# EDA.net
KiCad netlist of a schematic drawn in EasyEDA Pro
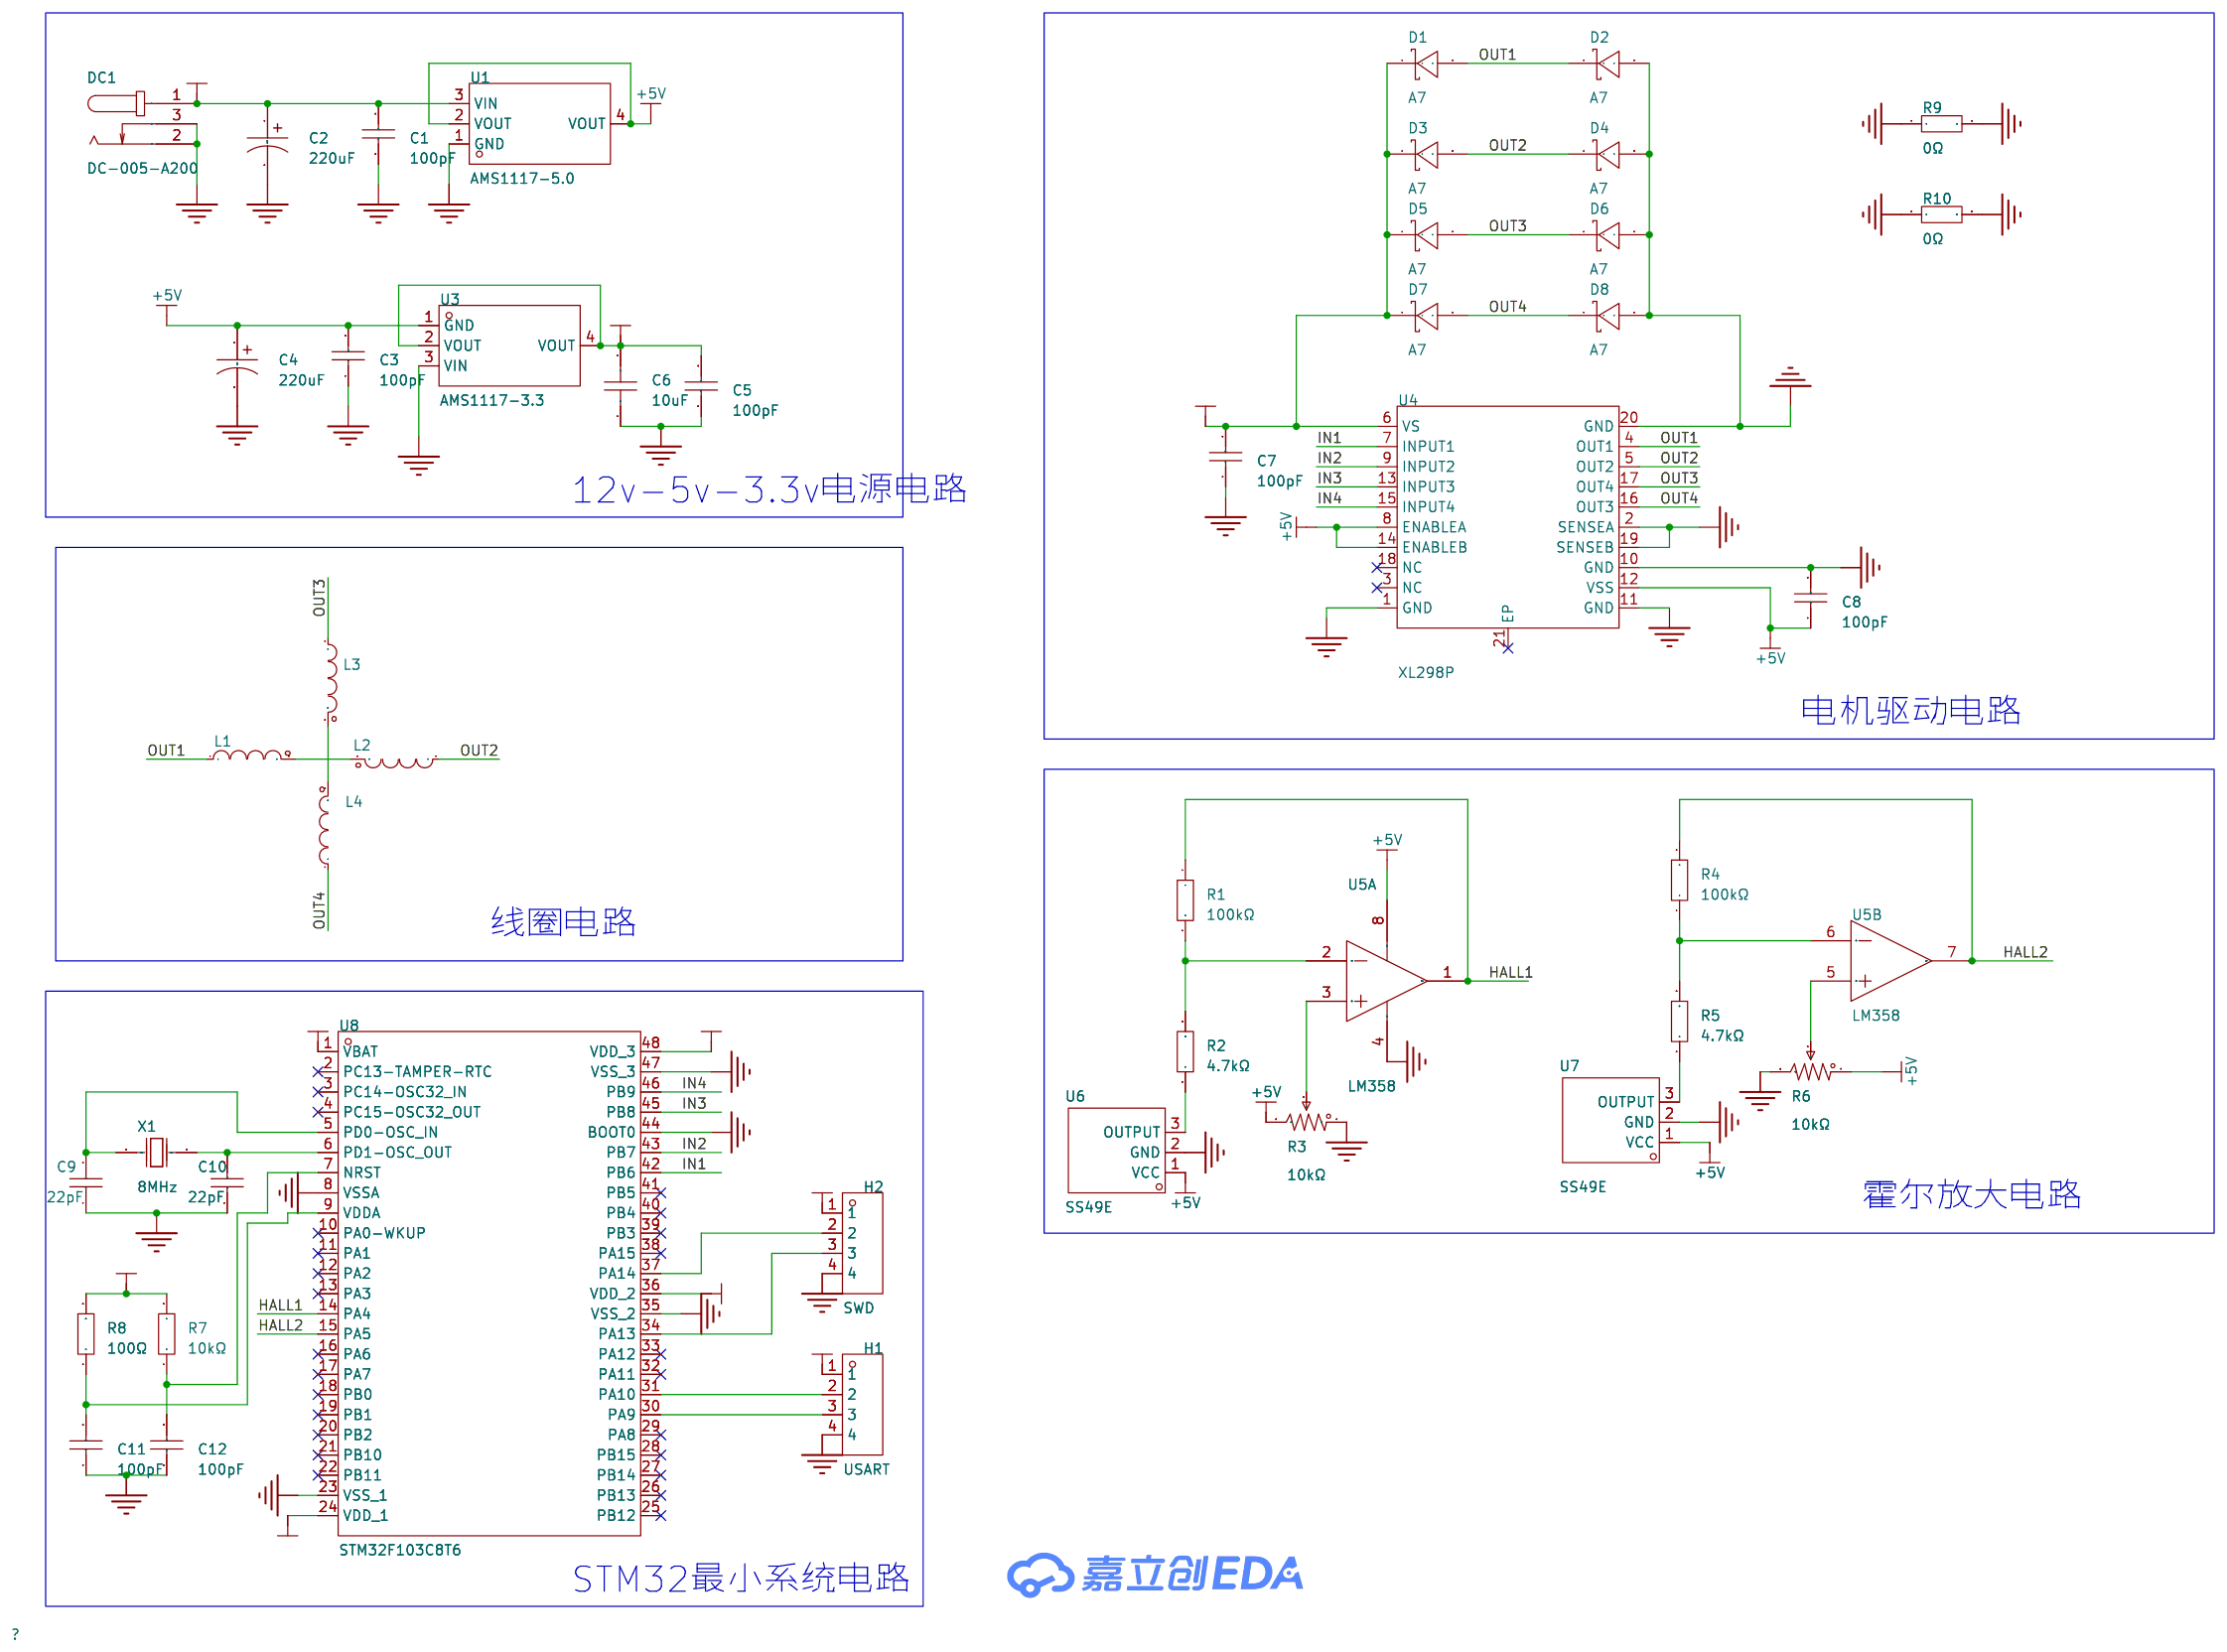
[diagram p0: schematic sheet]

(export (version "E")
  (design (tool "Eeschema 10.0.6"))
  (components
    (comp (ref "C1")
      (value "100pF")
      (footprint "easyedapro:C0805")
      (description "容值:100pF;精度:±5%;额定电压:50V;材质(温度系数):C0G;")
      (fields
        (field (name "Manufacturer Part") "CL21C101JBANNNC")
        (field (name "Manufacturer") "SAMSUNG(三星)")
      )
      (libsource (lib "easyedapro") (part "CL21C101JBANNNC"))
    )
    (comp (ref "C2")
      (value "220uF")
      (footprint "easyedapro:CAP-SMD_BD10.0-L10.3-W10.3-LS11.3-FD")
      (description "容值:220uF;精度:±20%;额定电压:50V;")
      (fields (field (name "Manufacturer Part") "HV1H227M1010PZ") (field (name "Manufacturer") "HONOR(荣誉)"))
      (libsource (lib "easyedapro") (part "HV1H227M1010PZ"))
    )
    (comp (ref "C3")
      (value "100pF")
      (footprint "easyedapro:C0805")
      (description "容值:100pF;精度:±5%;额定电压:50V;材质(温度系数):C0G;")
      (fields
        (field (name "Manufacturer Part") "CL21C101JBANNNC")
        (field (name "Manufacturer") "SAMSUNG(三星)")
      )
      (libsource (lib "easyedapro") (part "CL21C101JBANNNC"))
    )
    (comp (ref "C4")
      (value "220uF")
      (footprint "easyedapro:CAP-SMD_BD10.0-L10.3-W10.3-LS11.3-FD")
      (description "容值:220uF;精度:±20%;额定电压:50V;")
      (fields (field (name "Manufacturer Part") "HV1H227M1010PZ") (field (name "Manufacturer") "HONOR(荣誉)"))
      (libsource (lib "easyedapro") (part "HV1H227M1010PZ"))
    )
    (comp (ref "C5")
      (value "100pF")
      (footprint "easyedapro:C0805")
      (description "容值:100pF;精度:±5%;额定电压:50V;材质(温度系数):C0G;")
      (fields
        (field (name "Manufacturer Part") "CL21C101JBANNNC")
        (field (name "Manufacturer") "SAMSUNG(三星)")
      )
      (libsource (lib "easyedapro") (part "CL21C101JBANNNC"))
    )
    (comp (ref "C6")
      (value "10uF")
      (footprint "easyedapro:C0805")
      (description "容值:10uF;精度:±10%;额定电压:50V;材质(温度系数):X5R;")
      (fields
        (field (name "Manufacturer Part") "GRM21BR61H106KE43L")
        (field (name "Manufacturer") "muRata(村田)")
      )
      (libsource (lib "easyedapro") (part "GRM21BR61H106KE43L"))
    )
    (comp (ref "C7")
      (value "100pF")
      (footprint "easyedapro:C0805")
      (description "容值:100pF;精度:±5%;额定电压:50V;材质(温度系数):C0G;")
      (fields
        (field (name "Manufacturer Part") "CL21C101JBANNNC")
        (field (name "Manufacturer") "SAMSUNG(三星)")
      )
      (libsource (lib "easyedapro") (part "CL21C101JBANNNC"))
    )
    (comp (ref "C8")
      (value "100pF")
      (footprint "easyedapro:C0805")
      (description "容值:100pF;精度:±5%;额定电压:50V;材质(温度系数):C0G;")
      (fields
        (field (name "Manufacturer Part") "CL21C101JBANNNC")
        (field (name "Manufacturer") "SAMSUNG(三星)")
      )
      (libsource (lib "easyedapro") (part "CL21C101JBANNNC"))
    )
    (comp (ref "C9")
      (value "22pF")
      (footprint "easyedapro:C0805")
      (description "容值:22pF;精度:±5%;额定电压:50V;材质(温度系数):C0G;")
      (fields
        (field (name "Manufacturer Part") "CL21C220JBANNNC")
        (field (name "Manufacturer") "SAMSUNG(三星)")
      )
      (libsource (lib "easyedapro") (part "CL21C220JBANNNC"))
    )
    (comp (ref "C10")
      (value "22pF")
      (footprint "easyedapro:C0805")
      (description "容值:22pF;精度:±5%;额定电压:50V;材质(温度系数):C0G;")
      (fields
        (field (name "Manufacturer Part") "CL21C220JBANNNC")
        (field (name "Manufacturer") "SAMSUNG(三星)")
      )
      (libsource (lib "easyedapro") (part "CL21C220JBANNNC"))
    )
    (comp (ref "C11")
      (value "100pF")
      (footprint "easyedapro:C0805")
      (description "容值:100pF;精度:±5%;额定电压:50V;材质(温度系数):C0G;")
      (fields
        (field (name "Manufacturer Part") "CL21C101JBANNNC")
        (field (name "Manufacturer") "SAMSUNG(三星)")
      )
      (libsource (lib "easyedapro") (part "CL21C101JBANNNC"))
    )
    (comp (ref "C12")
      (value "100pF")
      (footprint "easyedapro:C0805")
      (description "容值:100pF;精度:±5%;额定电压:50V;材质(温度系数):C0G;")
      (fields
        (field (name "Manufacturer Part") "CL21C101JBANNNC")
        (field (name "Manufacturer") "SAMSUNG(三星)")
      )
      (libsource (lib "easyedapro") (part "CL21C101JBANNNC"))
    )
    (comp (ref "D1")
      (value "A7")
      (footprint "easyedapro:SOD-123FL_L2.8-W1.8-LS3.7-RD")
      (description "二极管配置:独立式;正向压降(Vf):1.1V@1A;直流反向耐压(Vr):1kV;整流电流:1A;")
      (fields (field (name "Manufacturer") "GOODWORK(固得沃克)"))
      (libsource (lib "easyedapro") (part "A7_C2891324"))
    )
    (comp (ref "D2")
      (value "A7")
      (footprint "easyedapro:SOD-123FL_L2.8-W1.8-LS3.7-RD")
      (description "二极管配置:独立式;正向压降(Vf):1.1V@1A;直流反向耐压(Vr):1kV;整流电流:1A;")
      (fields (field (name "Manufacturer") "GOODWORK(固得沃克)"))
      (libsource (lib "easyedapro") (part "A7_C2891324"))
    )
    (comp (ref "D3")
      (value "A7")
      (footprint "easyedapro:SOD-123FL_L2.8-W1.8-LS3.7-RD")
      (description "二极管配置:独立式;正向压降(Vf):1.1V@1A;直流反向耐压(Vr):1kV;整流电流:1A;")
      (fields (field (name "Manufacturer") "GOODWORK(固得沃克)"))
      (libsource (lib "easyedapro") (part "A7_C2891324"))
    )
    (comp (ref "D4")
      (value "A7")
      (footprint "easyedapro:SOD-123FL_L2.8-W1.8-LS3.7-RD")
      (description "二极管配置:独立式;正向压降(Vf):1.1V@1A;直流反向耐压(Vr):1kV;整流电流:1A;")
      (fields (field (name "Manufacturer") "GOODWORK(固得沃克)"))
      (libsource (lib "easyedapro") (part "A7_C2891324"))
    )
    (comp (ref "D5")
      (value "A7")
      (footprint "easyedapro:SOD-123FL_L2.8-W1.8-LS3.7-RD")
      (description "二极管配置:独立式;正向压降(Vf):1.1V@1A;直流反向耐压(Vr):1kV;整流电流:1A;")
      (fields (field (name "Manufacturer") "GOODWORK(固得沃克)"))
      (libsource (lib "easyedapro") (part "A7_C2891324"))
    )
    (comp (ref "D6")
      (value "A7")
      (footprint "easyedapro:SOD-123FL_L2.8-W1.8-LS3.7-RD")
      (description "二极管配置:独立式;正向压降(Vf):1.1V@1A;直流反向耐压(Vr):1kV;整流电流:1A;")
      (fields (field (name "Manufacturer") "GOODWORK(固得沃克)"))
      (libsource (lib "easyedapro") (part "A7_C2891324"))
    )
    (comp (ref "D7")
      (value "A7")
      (footprint "easyedapro:SOD-123FL_L2.8-W1.8-LS3.7-RD")
      (description "二极管配置:独立式;正向压降(Vf):1.1V@1A;直流反向耐压(Vr):1kV;整流电流:1A;")
      (fields (field (name "Manufacturer") "GOODWORK(固得沃克)"))
      (libsource (lib "easyedapro") (part "A7_C2891324"))
    )
    (comp (ref "D8")
      (value "A7")
      (footprint "easyedapro:SOD-123FL_L2.8-W1.8-LS3.7-RD")
      (description "二极管配置:独立式;正向压降(Vf):1.1V@1A;直流反向耐压(Vr):1kV;整流电流:1A;")
      (fields (field (name "Manufacturer") "GOODWORK(固得沃克)"))
      (libsource (lib "easyedapro") (part "A7_C2891324"))
    )
    (comp (ref "DC1")
      (value "DC-005-A200")
      (footprint "easyedapro:DC-IN-TH_DC-005-A200")
      (description "连接器类型:DC电源插座;安装方式:弯插;触点内径:2mm;触点外径:6.4mm;额定电流:3A;额定电压:30V;工作温度范围:-20°C~+70°C;")
      (fields (field (name "Manufacturer") "XUNPU(讯普)"))
      (libsource (lib "easyedapro") (part "DC-005-A200"))
    )
    (comp (ref "H1")
      (value "USART")
      (footprint "easyedapro:HDR-TH_4P-P2.54-V-M")
      (fields (field (name "Manufacturer") "XFCN(兴飞)"))
      (libsource (lib "easyedapro") (part "PZ254V-11-04P_C2691448"))
    )
    (comp (ref "H2")
      (value "SWD")
      (footprint "easyedapro:HDR-TH_4P-P2.54-V-M")
      (fields (field (name "Manufacturer") "XFCN(兴飞)"))
      (libsource (lib "easyedapro") (part "PZ254V-11-04P_C2691448"))
    )
    (comp (ref "L1")
      (value "~")
      (footprint "easyedapro:L_INVERTER2_2.1")
      (libsource (lib "easyedapro") (part "L-6Ω-3.54"))
    )
    (comp (ref "L2")
      (value "~")
      (footprint "easyedapro:L_INVERTER2_2.1")
      (libsource (lib "easyedapro") (part "L-6Ω-3.54"))
    )
    (comp (ref "L3")
      (value "~")
      (footprint "easyedapro:L_INVERTER2_2.1")
      (libsource (lib "easyedapro") (part "L-6Ω-3.54"))
    )
    (comp (ref "L4")
      (value "~")
      (footprint "easyedapro:L_INVERTER2_2.1")
      (libsource (lib "easyedapro") (part "L-6Ω-3.54"))
    )
    (comp (ref "R1")
      (value "100kΩ")
      (footprint "easyedapro:R0805")
      (description "电阻类型:厚膜电阻;阻值:100kΩ;精度:±1%;功率:125mW;最大工作电压:150V;温度系数:±100ppm/°C;")
      (fields
        (field (name "Manufacturer Part") "0805W8F1003T5E")
        (field (name "Manufacturer") "UNI-ROYAL(厚声)")
      )
      (libsource (lib "easyedapro") (part "0805W8F1003T5E_C149504"))
    )
    (comp (ref "R2")
      (value "4.7kΩ")
      (footprint "easyedapro:R0805")
      (description "电阻类型:厚膜电阻;阻值:4.7kΩ;精度:±1%;功率:125mW;最大工作电压:150V;温度系数:±100ppm/°C;")
      (fields
        (field (name "Manufacturer Part") "0805W8F4701T5E")
        (field (name "Manufacturer") "UNI-ROYAL(厚声)")
      )
      (libsource (lib "easyedapro") (part "0805W8F4701T5E"))
    )
    (comp (ref "R3")
      (value "10kΩ")
      (footprint "easyedapro:RES-ADJ-TH_3P-L10.0-W10.0-P2.50-L")
      (description "阻值:10kΩ;精度:±10%;")
      (fields (field (name "Manufacturer Part") "3296W-1-103") (field (name "Manufacturer") "BOCHEN(博晨)"))
      (libsource (lib "easyedapro") (part "3296W-1-103"))
    )
    (comp (ref "R4")
      (value "100kΩ")
      (footprint "easyedapro:R0805")
      (description "电阻类型:厚膜电阻;阻值:100kΩ;精度:±1%;功率:125mW;最大工作电压:150V;温度系数:±100ppm/°C;")
      (fields
        (field (name "Manufacturer Part") "0805W8F1003T5E")
        (field (name "Manufacturer") "UNI-ROYAL(厚声)")
      )
      (libsource (lib "easyedapro") (part "0805W8F1003T5E_C149504"))
    )
    (comp (ref "R5")
      (value "4.7kΩ")
      (footprint "easyedapro:R0805")
      (description "电阻类型:厚膜电阻;阻值:4.7kΩ;精度:±1%;功率:125mW;最大工作电压:150V;温度系数:±100ppm/°C;")
      (fields
        (field (name "Manufacturer Part") "0805W8F4701T5E")
        (field (name "Manufacturer") "UNI-ROYAL(厚声)")
      )
      (libsource (lib "easyedapro") (part "0805W8F4701T5E"))
    )
    (comp (ref "R6")
      (value "10kΩ")
      (footprint "easyedapro:RES-ADJ-TH_3P-L10.0-W10.0-P2.50-L")
      (description "阻值:10kΩ;精度:±10%;")
      (fields (field (name "Manufacturer Part") "3296W-1-103") (field (name "Manufacturer") "BOCHEN(博晨)"))
      (libsource (lib "easyedapro") (part "3296W-1-103"))
    )
    (comp (ref "R7")
      (value "10kΩ")
      (footprint "easyedapro:R0805")
      (description "电阻类型:厚膜电阻;阻值:10kΩ;精度:±1%;功率:125mW;最大工作电压:150V;温度系数:±100ppm/°C;")
      (fields
        (field (name "Manufacturer Part") "0805W8F1002T5E")
        (field (name "Manufacturer") "UNI-ROYAL(厚声)")
      )
      (libsource (lib "easyedapro") (part "0805W8F1002T5E"))
    )
    (comp (ref "R8")
      (value "100Ω")
      (footprint "easyedapro:R0805")
      (description "电阻类型:厚膜电阻;阻值:100Ω;精度:±1%;功率:125mW;最大工作电压:150V;温度系数:±100ppm/°C;")
      (fields
        (field (name "Manufacturer Part") "0805W8F1000T5E")
        (field (name "Manufacturer") "UNI-ROYAL(厚声)")
      )
      (libsource (lib "easyedapro") (part "0805W8F1000T5E"))
    )
    (comp (ref "R9")
      (value "0Ω")
      (footprint "easyedapro:R0805")
      (description "电阻类型:厚膜电阻;阻值:0Ω;精度:±1%;功率:125mW;最大工作电压:150V;温度系数:±800ppm/°C;")
      (fields
        (field (name "Manufacturer Part") "0805W8F0000T5E")
        (field (name "Manufacturer") "UNI-ROYAL(厚声)")
      )
      (libsource (lib "easyedapro") (part "0805W8F0000T5E"))
    )
    (comp (ref "R10")
      (value "0Ω")
      (footprint "easyedapro:R0805")
      (description "电阻类型:厚膜电阻;阻值:0Ω;精度:±1%;功率:125mW;最大工作电压:150V;温度系数:±800ppm/°C;")
      (fields
        (field (name "Manufacturer Part") "0805W8F0000T5E")
        (field (name "Manufacturer") "UNI-ROYAL(厚声)")
      )
      (libsource (lib "easyedapro") (part "0805W8F0000T5E"))
    )
    (comp (ref "U1")
      (value "AMS1117-5.0")
      (footprint "easyedapro:SOT-223_L6.5-W3.5-P2.30-LS7.0-BR")
      (description "输出类型:固定;最大输入电压:12V;输出电压:5V;最大输出电流:1A;电源纹波抑制比(PSRR):68dB@(120Hz);输出极性:正极;")
      (fields (field (name "Manufacturer") "AMS"))
      (libsource (lib "easyedapro") (part "AMS1117-5.0"))
    )
    (comp (ref "U3")
      (value "AMS1117-3.3")
      (footprint "easyedapro:SOT-223-3_L6.5-W3.4-P2.30-LS7.0-BR")
      (description "输出类型:固定;最大输入电压:-;输出电压:3.3V;最大输出电流:1A;电源纹波抑制比(PSRR):72dB@(120Hz);输出极性:正极;")
      (fields (field (name "Manufacturer") "AMS"))
      (libsource (lib "easyedapro") (part "AMS1117-3.3"))
    )
    (comp (ref "U4")
      (value "XL298P")
      (footprint "easyedapro:HSOP-20_L15.9-W11.0-P1.27-LS14.2-BL-EP")
      (fields (field (name "Manufacturer") "XINLUDA(信路达)"))
      (libsource (lib "easyedapro") (part "XL298P"))
    )
    (comp (ref "U5")
      (value "LM358")
      (footprint "easyedapro:SOP-8_L4.9-W3.9-P1.27-LS6.0-BL")
      (description "放大器数:双路;增益带宽积(GBP):1.2MHz;输入偏置电流(Ib):50nA;输入失调电压(Vos):5mV;")
      (fields (field (name "Manufacturer") "MSKSEMI(美森科)"))
      (libsource (lib "easyedapro") (part "LM358_C5252902"))
    )
    (comp (ref "U6")
      (value "SS49E")
      (footprint "easyedapro:TO-92S_3P-L4.1-W1.6-P1.27-L")
      (description "线性霍尔效应传感器")
      (fields (field (name "Manufacturer") "Honeywell(霍尼韦尔)"))
      (libsource (lib "easyedapro") (part "SS49E"))
    )
    (comp (ref "U7")
      (value "SS49E")
      (footprint "easyedapro:TO-92S_3P-L4.1-W1.6-P1.27-L")
      (description "线性霍尔效应传感器")
      (fields (field (name "Manufacturer") "Honeywell(霍尼韦尔)"))
      (libsource (lib "easyedapro") (part "SS49E"))
    )
    (comp (ref "U8")
      (value "STM32F103C8T6")
      (footprint "easyedapro:LQFP-48_L7.0-W7.0-P0.50-LS9.0-BL")
      (description "CPU内核:ARM-M3;CPU最大主频:72MHz;应用领域:-;")
      (fields (field (name "Manufacturer") "ST(意法半导体)"))
      (libsource (lib "easyedapro") (part "STM32F103C8T6"))
    )
    (comp (ref "X1")
      (value "8MHz")
      (footprint "easyedapro:CRYSTAL-SMD_L11.5-W4.8-LS12.7")
      (description "晶振类型:贴片晶振;频率:8MHz;常温频差:±20ppm;外接负载电容:20pF;频率稳定度(全温):±30ppm;")
      (fields (field (name "Manufacturer Part") "X49SM8MSD2SC") (field (name "Manufacturer") "YXC(扬兴晶振)"))
      (libsource (lib "easyedapro") (part "X49SM8MSD2SC"))
    )
  )
  (nets
    (net (code "1") (name "+3.3V") (class "Default")
      (node (ref "C5") (pin "2") (pinfunction "2_2") (pintype "input"))
      (node (ref "C6") (pin "2") (pinfunction "2_2") (pintype "unspecified"))
      (node (ref "H1") (pin "1") (pinfunction "1_1") (pintype "unspecified"))
      (node (ref "H2") (pin "1") (pinfunction "1_1") (pintype "unspecified"))
      (node (ref "R7") (pin "2") (pinfunction "2_2") (pintype "input"))
      (node (ref "R8") (pin "2") (pinfunction "2_2") (pintype "input"))
      (node (ref "U3") (pin "2") (pinfunction "VOUT_2") (pintype "unspecified"))
      (node (ref "U3") (pin "4") (pinfunction "VOUT_4") (pintype "unspecified"))
      (node (ref "U8") (pin "1") (pinfunction "VBAT_1") (pintype "unspecified"))
      (node (ref "U8") (pin "24") (pinfunction "VDD_1_24") (pintype "unspecified"))
      (node (ref "U8") (pin "36") (pinfunction "VDD_2_36") (pintype "unspecified"))
      (node (ref "U8") (pin "48") (pinfunction "VDD_3_48") (pintype "unspecified"))
    )
    (net (code "2") (name "+5V") (class "Default")
      (node (ref "C3") (pin "2") (pinfunction "2_2") (pintype "input"))
      (node (ref "C4") (pin "1") (pinfunction "1_1") (pintype "unspecified"))
      (node (ref "C8") (pin "1") (pinfunction "1_1") (pintype "input"))
      (node (ref "R3") (pin "3") (pinfunction "3_3") (pintype "unspecified"))
      (node (ref "R6") (pin "1") (pinfunction "1_1") (pintype "unspecified"))
      (node (ref "U1") (pin "2") (pinfunction "VOUT_2") (pintype "unspecified"))
      (node (ref "U1") (pin "4") (pinfunction "VOUT_4") (pintype "unspecified"))
      (node (ref "U3") (pin "1") (pinfunction "GND_1") (pintype "unspecified"))
      (node (ref "U4") (pin "12") (pinfunction "VSS_12") (pintype "unspecified"))
      (node (ref "U4") (pin "14") (pinfunction "ENABLEB_14") (pintype "unspecified"))
      (node (ref "U4") (pin "8") (pinfunction "ENABLEA_8") (pintype "unspecified"))
      (node (ref "U5") (pin "8") (pinfunction "VCC_8") (pintype "unspecified"))
      (node (ref "U6") (pin "1") (pinfunction "VCC_1") (pintype "unspecified"))
      (node (ref "U7") (pin "1") (pinfunction "VCC_1") (pintype "unspecified"))
    )
    (net (code "3") (name "+12V") (class "Default")
      (node (ref "C1") (pin "2") (pinfunction "2_2") (pintype "input"))
      (node (ref "C2") (pin "1") (pinfunction "1_1") (pintype "unspecified"))
      (node (ref "C7") (pin "2") (pinfunction "2_2") (pintype "input"))
      (node (ref "D1") (pin "1") (pinfunction "K_1") (pintype "unspecified"))
      (node (ref "D3") (pin "1") (pinfunction "K_1") (pintype "unspecified"))
      (node (ref "D5") (pin "1") (pinfunction "K_1") (pintype "unspecified"))
      (node (ref "D7") (pin "1") (pinfunction "K_1") (pintype "unspecified"))
      (node (ref "DC1") (pin "1") (pinfunction "1_1") (pintype "unspecified"))
      (node (ref "U1") (pin "3") (pinfunction "VIN_3") (pintype "unspecified"))
      (node (ref "U4") (pin "6") (pinfunction "VS_6") (pintype "unspecified"))
    )
    (net (code "4") (name "/HALL1") (class "Default")
      (node (ref "R1") (pin "1") (pinfunction "1_1") (pintype "unspecified"))
      (node (ref "U5") (pin "1") (pinfunction "OUT1_1") (pintype "unspecified"))
      (node (ref "U8") (pin "14") (pinfunction "PA4_14") (pintype "unspecified"))
    )
    (net (code "5") (name "/HALL2") (class "Default")
      (node (ref "R4") (pin "2") (pinfunction "2_2") (pintype "unspecified"))
      (node (ref "U5") (pin "7") (pinfunction "OUT2_7") (pintype "unspecified"))
      (node (ref "U8") (pin "15") (pinfunction "PA5_15") (pintype "unspecified"))
    )
    (net (code "6") (name "/IN1") (class "Default")
      (node (ref "U4") (pin "7") (pinfunction "INPUT1_7") (pintype "unspecified"))
      (node (ref "U8") (pin "42") (pinfunction "PB6_42") (pintype "unspecified"))
    )
    (net (code "7") (name "/IN2") (class "Default")
      (node (ref "U4") (pin "9") (pinfunction "INPUT2_9") (pintype "unspecified"))
      (node (ref "U8") (pin "43") (pinfunction "PB7_43") (pintype "unspecified"))
    )
    (net (code "8") (name "/IN3") (class "Default")
      (node (ref "U4") (pin "13") (pinfunction "INPUT3_13") (pintype "unspecified"))
      (node (ref "U8") (pin "45") (pinfunction "PB8_45") (pintype "unspecified"))
    )
    (net (code "9") (name "/IN4") (class "Default")
      (node (ref "U4") (pin "15") (pinfunction "INPUT4_15") (pintype "unspecified"))
      (node (ref "U8") (pin "46") (pinfunction "PB9_46") (pintype "unspecified"))
    )
    (net (code "10") (name "/OUT1") (class "Default")
      (node (ref "D1") (pin "2") (pinfunction "A_2") (pintype "unspecified"))
      (node (ref "D2") (pin "1") (pinfunction "K_1") (pintype "unspecified"))
      (node (ref "L1") (pin "1") (pinfunction "1_1") (pintype "unspecified"))
      (node (ref "U4") (pin "4") (pinfunction "OUT1_4") (pintype "unspecified"))
    )
    (net (code "11") (name "/OUT2") (class "Default")
      (node (ref "D3") (pin "2") (pinfunction "A_2") (pintype "unspecified"))
      (node (ref "D4") (pin "1") (pinfunction "K_1") (pintype "unspecified"))
      (node (ref "L2") (pin "1") (pinfunction "1_1") (pintype "unspecified"))
      (node (ref "U4") (pin "5") (pinfunction "OUT2_5") (pintype "unspecified"))
    )
    (net (code "12") (name "/OUT3") (class "Default")
      (node (ref "D5") (pin "2") (pinfunction "A_2") (pintype "unspecified"))
      (node (ref "D6") (pin "1") (pinfunction "K_1") (pintype "unspecified"))
      (node (ref "L3") (pin "1") (pinfunction "1_1") (pintype "unspecified"))
      (node (ref "U4") (pin "17") (pinfunction "OUT4_17") (pintype "unspecified"))
    )
    (net (code "13") (name "/OUT4") (class "Default")
      (node (ref "D7") (pin "2") (pinfunction "A_2") (pintype "unspecified"))
      (node (ref "D8") (pin "1") (pinfunction "K_1") (pintype "unspecified"))
      (node (ref "L4") (pin "1") (pinfunction "1_1") (pintype "unspecified"))
      (node (ref "U4") (pin "16") (pinfunction "OUT3_16") (pintype "unspecified"))
    )
    (net (code "14") (name "AGND") (class "Default")
      (node (ref "C3") (pin "1") (pinfunction "1_1") (pintype "input"))
      (node (ref "C4") (pin "2") (pinfunction "2_2") (pintype "unspecified"))
      (node (ref "R10") (pin "1") (pinfunction "1_1") (pintype "input"))
      (node (ref "R3") (pin "1") (pinfunction "1_1") (pintype "unspecified"))
      (node (ref "R6") (pin "3") (pinfunction "3_3") (pintype "unspecified"))
      (node (ref "U1") (pin "1") (pinfunction "GND_1") (pintype "unspecified"))
      (node (ref "U5") (pin "4") (pinfunction "VEE_4") (pintype "unspecified"))
      (node (ref "U6") (pin "2") (pinfunction "GND_2") (pintype "unspecified"))
      (node (ref "U7") (pin "2") (pinfunction "GND_2") (pintype "unspecified"))
    )
    (net (code "15") (name "GND") (class "Default")
      (node (ref "C10") (pin "1") (pinfunction "1_1") (pintype "input"))
      (node (ref "C11") (pin "1") (pinfunction "1_1") (pintype "input"))
      (node (ref "C12") (pin "1") (pinfunction "1_1") (pintype "input"))
      (node (ref "C5") (pin "1") (pinfunction "1_1") (pintype "input"))
      (node (ref "C6") (pin "1") (pinfunction "1_1") (pintype "unspecified"))
      (node (ref "C9") (pin "1") (pinfunction "1_1") (pintype "input"))
      (node (ref "H1") (pin "4") (pinfunction "4_4") (pintype "unspecified"))
      (node (ref "H2") (pin "4") (pinfunction "4_4") (pintype "unspecified"))
      (node (ref "R10") (pin "2") (pinfunction "2_2") (pintype "input"))
      (node (ref "R9") (pin "2") (pinfunction "2_2") (pintype "input"))
      (node (ref "U3") (pin "3") (pinfunction "VIN_3") (pintype "unspecified"))
      (node (ref "U8") (pin "23") (pinfunction "VSS_1_23") (pintype "unspecified"))
      (node (ref "U8") (pin "35") (pinfunction "VSS_2_35") (pintype "unspecified"))
      (node (ref "U8") (pin "44") (pinfunction "BOOT0_44") (pintype "unspecified"))
      (node (ref "U8") (pin "47") (pinfunction "VSS_3_47") (pintype "unspecified"))
      (node (ref "U8") (pin "8") (pinfunction "VSSA_8") (pintype "unspecified"))
    )
    (net (code "16") (name "Net-(L1-Pad2)") (class "Default")
      (node (ref "L1") (pin "2") (pinfunction "2_2") (pintype "unspecified"))
      (node (ref "L2") (pin "2") (pinfunction "2_2") (pintype "unspecified"))
    )
    (net (code "17") (name "Net-(L3-Pad2)") (class "Default")
      (node (ref "L3") (pin "2") (pinfunction "2_2") (pintype "unspecified"))
      (node (ref "L4") (pin "2") (pinfunction "2_2") (pintype "unspecified"))
    )
    (net (code "18") (name "Net-(U5A-IN1+)") (class "Default")
      (node (ref "R3") (pin "2") (pinfunction "2_2") (pintype "unspecified"))
      (node (ref "U5") (pin "3") (pinfunction "IN1+_3") (pintype "unspecified"))
    )
    (net (code "19") (name "Net-(U5A-IN1-)") (class "Default")
      (node (ref "R1") (pin "2") (pinfunction "2_2") (pintype "unspecified"))
      (node (ref "R2") (pin "2") (pinfunction "2_2") (pintype "input"))
      (node (ref "U5") (pin "2") (pinfunction "IN1-_2") (pintype "unspecified"))
    )
    (net (code "20") (name "Net-(U5B-IN2+)") (class "Default")
      (node (ref "R6") (pin "2") (pinfunction "2_2") (pintype "unspecified"))
      (node (ref "U5") (pin "5") (pinfunction "IN2+_5") (pintype "unspecified"))
    )
    (net (code "21") (name "Net-(U5B-IN2-)") (class "Default")
      (node (ref "R4") (pin "1") (pinfunction "1_1") (pintype "unspecified"))
      (node (ref "R5") (pin "2") (pinfunction "2_2") (pintype "input"))
      (node (ref "U5") (pin "6") (pinfunction "IN2-_6") (pintype "unspecified"))
    )
    (net (code "22") (name "Net-(U6-OUTPUT)") (class "Default")
      (node (ref "R2") (pin "1") (pinfunction "1_1") (pintype "input"))
      (node (ref "U6") (pin "3") (pinfunction "OUTPUT_3") (pintype "unspecified"))
    )
    (net (code "23") (name "Net-(U7-OUTPUT)") (class "Default")
      (node (ref "R5") (pin "1") (pinfunction "1_1") (pintype "input"))
      (node (ref "U7") (pin "3") (pinfunction "OUTPUT_3") (pintype "unspecified"))
    )
    (net (code "24") (name "Net-(U8-NRST)") (class "Default")
      (node (ref "C12") (pin "2") (pinfunction "2_2") (pintype "input"))
      (node (ref "R7") (pin "1") (pinfunction "1_1") (pintype "input"))
      (node (ref "U8") (pin "7") (pinfunction "NRST_7") (pintype "unspecified"))
    )
    (net (code "25") (name "Net-(U8-PA9)") (class "Default")
      (node (ref "H1") (pin "3") (pinfunction "3_3") (pintype "unspecified"))
      (node (ref "U8") (pin "30") (pinfunction "PA9_30") (pintype "unspecified"))
    )
    (net (code "26") (name "Net-(U8-PA10)") (class "Default")
      (node (ref "H1") (pin "2") (pinfunction "2_2") (pintype "unspecified"))
      (node (ref "U8") (pin "31") (pinfunction "PA10_31") (pintype "unspecified"))
    )
    (net (code "27") (name "Net-(U8-PA13)") (class "Default")
      (node (ref "H2") (pin "3") (pinfunction "3_3") (pintype "unspecified"))
      (node (ref "U8") (pin "34") (pinfunction "PA13_34") (pintype "unspecified"))
    )
    (net (code "28") (name "Net-(U8-PA14)") (class "Default")
      (node (ref "H2") (pin "2") (pinfunction "2_2") (pintype "unspecified"))
      (node (ref "U8") (pin "37") (pinfunction "PA14_37") (pintype "unspecified"))
    )
    (net (code "29") (name "Net-(U8-PD0-OSC_IN)") (class "Default")
      (node (ref "C9") (pin "2") (pinfunction "2_2") (pintype "input"))
      (node (ref "U8") (pin "5") (pinfunction "PD0-OSC_IN_5") (pintype "unspecified"))
      (node (ref "X1") (pin "2") (pinfunction "OSC2_2") (pintype "input"))
    )
    (net (code "30") (name "Net-(U8-PD1-OSC_OUT)") (class "Default")
      (node (ref "C10") (pin "2") (pinfunction "2_2") (pintype "input"))
      (node (ref "U8") (pin "6") (pinfunction "PD1-OSC_OUT_6") (pintype "unspecified"))
      (node (ref "X1") (pin "1") (pinfunction "OSC1_1") (pintype "input"))
    )
    (net (code "31") (name "Net-(U8-VDDA)") (class "Default")
      (node (ref "C11") (pin "2") (pinfunction "2_2") (pintype "input"))
      (node (ref "R8") (pin "1") (pinfunction "1_1") (pintype "input"))
      (node (ref "U8") (pin "9") (pinfunction "VDDA_9") (pintype "unspecified"))
    )
    (net (code "32") (name "PGND") (class "Default")
      (node (ref "C1") (pin "1") (pinfunction "1_1") (pintype "input"))
      (node (ref "C2") (pin "2") (pinfunction "2_2") (pintype "unspecified"))
      (node (ref "C7") (pin "1") (pinfunction "1_1") (pintype "input"))
      (node (ref "C8") (pin "2") (pinfunction "2_2") (pintype "input"))
      (node (ref "D2") (pin "2") (pinfunction "A_2") (pintype "unspecified"))
      (node (ref "D4") (pin "2") (pinfunction "A_2") (pintype "unspecified"))
      (node (ref "D6") (pin "2") (pinfunction "A_2") (pintype "unspecified"))
      (node (ref "D8") (pin "2") (pinfunction "A_2") (pintype "unspecified"))
      (node (ref "DC1") (pin "2") (pinfunction "2_2") (pintype "unspecified"))
      (node (ref "DC1") (pin "3") (pinfunction "3_3") (pintype "unspecified"))
      (node (ref "R9") (pin "1") (pinfunction "1_1") (pintype "input"))
      (node (ref "U4") (pin "1") (pinfunction "GND_1") (pintype "unspecified"))
      (node (ref "U4") (pin "10") (pinfunction "GND_10") (pintype "unspecified"))
      (node (ref "U4") (pin "11") (pinfunction "GND_11") (pintype "unspecified"))
      (node (ref "U4") (pin "19") (pinfunction "SENSEB_19") (pintype "unspecified"))
      (node (ref "U4") (pin "2") (pinfunction "SENSEA_2") (pintype "unspecified"))
      (node (ref "U4") (pin "20") (pinfunction "GND_20") (pintype "unspecified"))
    )
    (net (code "33") (name "unconnected-(U4-EP-Pad21)") (class "Default")
      (node (ref "U4") (pin "21") (pinfunction "EP_21") (pintype "unspecified+no_connect"))
    )
    (net (code "34") (name "unconnected-(U4-NC-Pad3)") (class "Default")
      (node (ref "U4") (pin "3") (pinfunction "NC_3") (pintype "unspecified+no_connect"))
    )
    (net (code "35") (name "unconnected-(U4-NC-Pad18)") (class "Default")
      (node (ref "U4") (pin "18") (pinfunction "NC_18") (pintype "unspecified+no_connect"))
    )
    (net (code "36") (name "unconnected-(U8-PA0-WKUP-Pad10)") (class "Default")
      (node (ref "U8") (pin "10") (pinfunction "PA0-WKUP_10") (pintype "unspecified+no_connect"))
    )
    (net (code "37") (name "unconnected-(U8-PA1-Pad11)") (class "Default")
      (node (ref "U8") (pin "11") (pinfunction "PA1_11") (pintype "unspecified+no_connect"))
    )
    (net (code "38") (name "unconnected-(U8-PA2-Pad12)") (class "Default")
      (node (ref "U8") (pin "12") (pinfunction "PA2_12") (pintype "unspecified+no_connect"))
    )
    (net (code "39") (name "unconnected-(U8-PA3-Pad13)") (class "Default")
      (node (ref "U8") (pin "13") (pinfunction "PA3_13") (pintype "unspecified+no_connect"))
    )
    (net (code "40") (name "unconnected-(U8-PA6-Pad16)") (class "Default")
      (node (ref "U8") (pin "16") (pinfunction "PA6_16") (pintype "unspecified+no_connect"))
    )
    (net (code "41") (name "unconnected-(U8-PA7-Pad17)") (class "Default")
      (node (ref "U8") (pin "17") (pinfunction "PA7_17") (pintype "unspecified+no_connect"))
    )
    (net (code "42") (name "unconnected-(U8-PA8-Pad29)") (class "Default")
      (node (ref "U8") (pin "29") (pinfunction "PA8_29") (pintype "unspecified+no_connect"))
    )
    (net (code "43") (name "unconnected-(U8-PA11-Pad32)") (class "Default")
      (node (ref "U8") (pin "32") (pinfunction "PA11_32") (pintype "unspecified+no_connect"))
    )
    (net (code "44") (name "unconnected-(U8-PA12-Pad33)") (class "Default")
      (node (ref "U8") (pin "33") (pinfunction "PA12_33") (pintype "unspecified+no_connect"))
    )
    (net (code "45") (name "unconnected-(U8-PA15-Pad38)") (class "Default")
      (node (ref "U8") (pin "38") (pinfunction "PA15_38") (pintype "unspecified+no_connect"))
    )
    (net (code "46") (name "unconnected-(U8-PB0-Pad18)") (class "Default")
      (node (ref "U8") (pin "18") (pinfunction "PB0_18") (pintype "unspecified+no_connect"))
    )
    (net (code "47") (name "unconnected-(U8-PB1-Pad19)") (class "Default")
      (node (ref "U8") (pin "19") (pinfunction "PB1_19") (pintype "unspecified+no_connect"))
    )
    (net (code "48") (name "unconnected-(U8-PB2-Pad20)") (class "Default")
      (node (ref "U8") (pin "20") (pinfunction "PB2_20") (pintype "unspecified+no_connect"))
    )
    (net (code "49") (name "unconnected-(U8-PB3-Pad39)") (class "Default")
      (node (ref "U8") (pin "39") (pinfunction "PB3_39") (pintype "unspecified+no_connect"))
    )
    (net (code "50") (name "unconnected-(U8-PB4-Pad40)") (class "Default")
      (node (ref "U8") (pin "40") (pinfunction "PB4_40") (pintype "unspecified+no_connect"))
    )
    (net (code "51") (name "unconnected-(U8-PB5-Pad41)") (class "Default")
      (node (ref "U8") (pin "41") (pinfunction "PB5_41") (pintype "unspecified+no_connect"))
    )
    (net (code "52") (name "unconnected-(U8-PB10-Pad21)") (class "Default")
      (node (ref "U8") (pin "21") (pinfunction "PB10_21") (pintype "unspecified+no_connect"))
    )
    (net (code "53") (name "unconnected-(U8-PB11-Pad22)") (class "Default")
      (node (ref "U8") (pin "22") (pinfunction "PB11_22") (pintype "unspecified+no_connect"))
    )
    (net (code "54") (name "unconnected-(U8-PB12-Pad25)") (class "Default")
      (node (ref "U8") (pin "25") (pinfunction "PB12_25") (pintype "unspecified+no_connect"))
    )
    (net (code "55") (name "unconnected-(U8-PB13-Pad26)") (class "Default")
      (node (ref "U8") (pin "26") (pinfunction "PB13_26") (pintype "unspecified+no_connect"))
    )
    (net (code "56") (name "unconnected-(U8-PB14-Pad27)") (class "Default")
      (node (ref "U8") (pin "27") (pinfunction "PB14_27") (pintype "unspecified+no_connect"))
    )
    (net (code "57") (name "unconnected-(U8-PB15-Pad28)") (class "Default")
      (node (ref "U8") (pin "28") (pinfunction "PB15_28") (pintype "unspecified+no_connect"))
    )
    (net (code "58") (name "unconnected-(U8-PC13-TAMPER-RTC-Pad2)") (class "Default")
      (node (ref "U8") (pin "2") (pinfunction "PC13-TAMPER-RTC_2") (pintype "unspecified+no_connect"))
    )
    (net (code "59") (name "unconnected-(U8-PC14-OSC32_IN-Pad3)") (class "Default")
      (node (ref "U8") (pin "3") (pinfunction "PC14-OSC32_IN_3") (pintype "unspecified+no_connect"))
    )
    (net (code "60") (name "unconnected-(U8-PC15-OSC32_OUT-Pad4)") (class "Default")
      (node (ref "U8") (pin "4") (pinfunction "PC15-OSC32_OUT_4") (pintype "unspecified+no_connect"))
    )
  )
)
